# Driver.net
KiCad netlist of a schematic drawn in Altium Designer
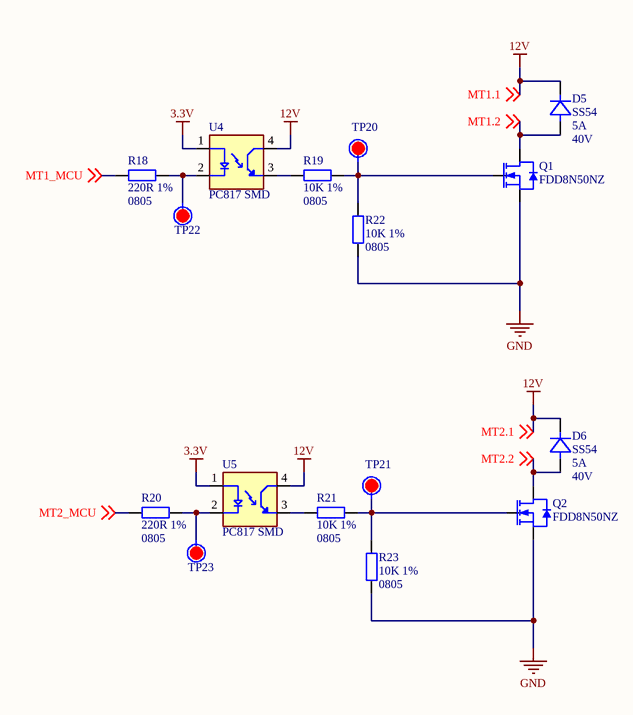
[diagram p0: Driver.SchDoc]

(export (version "E")
  (design (tool "Eeschema 10.0.6"))
  (components
    (comp (ref "D5")
      (value "SS54")
      (footprint "SMA")
      (description "DIODE SCHOTTKY 40V 5A SMA")
      (fields
        (field (name "MANUFACTURER") "EVVO")
        (field (name "CURRENT") "5A")
        (field (name "DC VOLTAGE") "40V")
      )
      (libsource (lib "Diode") (part "SS54"))
    )
    (comp (ref "D6")
      (value "SS54")
      (footprint "SMA")
      (description "DIODE SCHOTTKY 40V 5A SMA")
      (fields
        (field (name "MANUFACTURER") "EVVO")
        (field (name "CURRENT") "5A")
        (field (name "DC VOLTAGE") "40V")
      )
      (libsource (lib "Diode") (part "SS54"))
    )
    (comp (ref "Q1")
      (value "FDD8N50NZ")
      (footprint "TO252-2")
      (description "650V 7A 1 N-Channel TO-252 MOSFETs ROHS")
      (fields
        (field (name "MANUFACTURER") "VBsemi Elec")
        (field (name "MANUFACTURE PART NUMBER") "FDD8N50NZTM-VB")
      )
      (libsource (lib "Trans_Fets") (part "FDD8N50NZ"))
    )
    (comp (ref "Q2")
      (value "FDD8N50NZ")
      (footprint "TO252-2")
      (description "650V 7A 1 N-Channel TO-252 MOSFETs ROHS")
      (fields
        (field (name "MANUFACTURER") "VBsemi Elec")
        (field (name "MANUFACTURE PART NUMBER") "FDD8N50NZTM-VB")
      )
      (libsource (lib "Trans_Fets") (part "FDD8N50NZ"))
    )
    (comp (ref "R18")
      (value "220R 1%")
      (footprint "RES_SMD_0805")
      (fields
        (field (name "MANUFACTURER") "TE Connectivity Passive Product")
        (field (name "MANUFACTURE PART NUMBER") "CRGCQ0805F220R")
        (field (name "SIZE") "0805")
      )
      (libsource (lib "Resistors") (part "R0805_220R"))
    )
    (comp (ref "R19")
      (value "10K 1%")
      (footprint "RES_SMD_0805")
      (description "10 kOhms ±1% 0.125W, 1/8W Chip Resistor 0805 (2012 Metric) Moisture Resistant Thick Film")
      (fields
        (field (name "MANUFACTURER") "YAGEO")
        (field (name "MANUFACTURE PART NUMBER") "RC0805FR-0710KL")
        (field (name "SIZE") "0805")
      )
      (libsource (lib "Resistors") (part "R0805_10K"))
    )
    (comp (ref "R20")
      (value "220R 1%")
      (footprint "RES_SMD_0805")
      (fields
        (field (name "MANUFACTURER") "TE Connectivity Passive Product")
        (field (name "MANUFACTURE PART NUMBER") "CRGCQ0805F220R")
        (field (name "SIZE") "0805")
      )
      (libsource (lib "Resistors") (part "R0805_220R"))
    )
    (comp (ref "R21")
      (value "10K 1%")
      (footprint "RES_SMD_0805")
      (description "10 kOhms ±1% 0.125W, 1/8W Chip Resistor 0805 (2012 Metric) Moisture Resistant Thick Film")
      (fields
        (field (name "MANUFACTURER") "YAGEO")
        (field (name "MANUFACTURE PART NUMBER") "RC0805FR-0710KL")
        (field (name "SIZE") "0805")
      )
      (libsource (lib "Resistors") (part "R0805_10K"))
    )
    (comp (ref "R22")
      (value "10K 1%")
      (footprint "RES_SMD_0805")
      (description "10 kOhms ±1% 0.125W, 1/8W Chip Resistor 0805 (2012 Metric) Moisture Resistant Thick Film")
      (fields
        (field (name "MANUFACTURER") "YAGEO")
        (field (name "MANUFACTURE PART NUMBER") "RC0805FR-0710KL")
        (field (name "SIZE") "0805")
      )
      (libsource (lib "Resistors") (part "R0805_10K"))
    )
    (comp (ref "R23")
      (value "10K 1%")
      (footprint "RES_SMD_0805")
      (description "10 kOhms ±1% 0.125W, 1/8W Chip Resistor 0805 (2012 Metric) Moisture Resistant Thick Film")
      (fields
        (field (name "MANUFACTURER") "YAGEO")
        (field (name "MANUFACTURE PART NUMBER") "RC0805FR-0710KL")
        (field (name "SIZE") "0805")
      )
      (libsource (lib "Resistors") (part "R0805_10K"))
    )
    (comp (ref "TP20")
      (value "Test Point")
      (footprint "TEST_POINT")
      (libsource (lib "Connectors") (part "TEST_POINT"))
    )
    (comp (ref "TP21")
      (value "Test Point")
      (footprint "TEST_POINT")
      (libsource (lib "Connectors") (part "TEST_POINT"))
    )
    (comp (ref "TP22")
      (value "Test Point")
      (footprint "TEST_POINT")
      (libsource (lib "Connectors") (part "TEST_POINT"))
    )
    (comp (ref "TP23")
      (value "Test Point")
      (footprint "TEST_POINT")
      (libsource (lib "Connectors") (part "TEST_POINT"))
    )
    (comp (ref "U4")
      (value "PC817 SMD")
      (footprint "PC817XL_SMD")
      (description "Optoisolator Transistor Output 5000Vrms 1 Channel 4-SMD")
      (fields
        (field (name "MANUFACTURER") "American Bright Optoelectronics Corporation")
        (field (name "MANUFACTURE PART NUMBER") "APC-817C1-SL")
      )
      (libsource (lib "ICs") (part "PC817_SMD"))
    )
    (comp (ref "U5")
      (value "PC817 SMD")
      (footprint "PC817XL_SMD")
      (description "Optoisolator Transistor Output 5000Vrms 1 Channel 4-SMD")
      (fields
        (field (name "MANUFACTURER") "American Bright Optoelectronics Corporation")
        (field (name "MANUFACTURE PART NUMBER") "APC-817C1-SL")
      )
      (libsource (lib "ICs") (part "PC817_SMD"))
    )
  )
  (nets
    (net (code "1") (name "3.3V") (class "Default")
      (node (ref "U4") (pin "1") (pinfunction "A_1") (pintype "passive"))
      (node (ref "U5") (pin "1") (pinfunction "A_1") (pintype "passive"))
    )
    (net (code "2") (name "12V") (class "Default")
      (node (ref "D5") (pin "C") (pinfunction "C_C") (pintype "passive"))
      (node (ref "D6") (pin "C") (pinfunction "C_C") (pintype "passive"))
      (node (ref "U4") (pin "4") (pinfunction "CT_4") (pintype "passive"))
      (node (ref "U5") (pin "4") (pinfunction "CT_4") (pintype "passive"))
    )
    (net (code "3") (name "GND") (class "Default")
      (node (ref "Q1") (pin "3") (pinfunction "S_3") (pintype "passive"))
      (node (ref "Q2") (pin "3") (pinfunction "S_3") (pintype "passive"))
      (node (ref "R22") (pin "1") (pinfunction "1_1") (pintype "passive"))
      (node (ref "R23") (pin "1") (pinfunction "1_1") (pintype "passive"))
    )
    (net (code "4") (name "MT1.2") (class "Default")
      (node (ref "D5") (pin "A") (pinfunction "A_A") (pintype "passive"))
      (node (ref "Q1") (pin "2") (pinfunction "D_2") (pintype "passive"))
    )
    (net (code "5") (name "MT1_MCU") (class "Default")
      (node (ref "R18") (pin "2") (pinfunction "2_2") (pintype "passive"))
    )
    (net (code "6") (name "MT2.2") (class "Default")
      (node (ref "D6") (pin "A") (pinfunction "A_A") (pintype "passive"))
      (node (ref "Q2") (pin "2") (pinfunction "D_2") (pintype "passive"))
    )
    (net (code "7") (name "MT2_MCU") (class "Default")
      (node (ref "R20") (pin "2") (pinfunction "2_2") (pintype "passive"))
    )
    (net (code "8") (name "Net-(Q1-G)") (class "Default")
      (node (ref "Q1") (pin "1") (pinfunction "G_1") (pintype "passive"))
      (node (ref "R19") (pin "2") (pinfunction "2_2") (pintype "passive"))
      (node (ref "R22") (pin "2") (pinfunction "2_2") (pintype "passive"))
      (node (ref "TP20") (pin "1") (pinfunction "1_1") (pintype "passive"))
    )
    (net (code "9") (name "Net-(Q2-G)") (class "Default")
      (node (ref "Q2") (pin "1") (pinfunction "G_1") (pintype "passive"))
      (node (ref "R21") (pin "2") (pinfunction "2_2") (pintype "passive"))
      (node (ref "R23") (pin "2") (pinfunction "2_2") (pintype "passive"))
      (node (ref "TP21") (pin "1") (pinfunction "1_1") (pintype "passive"))
    )
    (net (code "10") (name "Net-(U4-C)") (class "Default")
      (node (ref "R18") (pin "1") (pinfunction "1_1") (pintype "passive"))
      (node (ref "TP22") (pin "1") (pinfunction "1_1") (pintype "passive"))
      (node (ref "U4") (pin "2") (pinfunction "C_2") (pintype "passive"))
    )
    (net (code "11") (name "Net-(U4-ET)") (class "Default")
      (node (ref "R19") (pin "1") (pinfunction "1_1") (pintype "passive"))
      (node (ref "U4") (pin "3") (pinfunction "ET_3") (pintype "passive"))
    )
    (net (code "12") (name "Net-(U5-C)") (class "Default")
      (node (ref "R20") (pin "1") (pinfunction "1_1") (pintype "passive"))
      (node (ref "TP23") (pin "1") (pinfunction "1_1") (pintype "passive"))
      (node (ref "U5") (pin "2") (pinfunction "C_2") (pintype "passive"))
    )
    (net (code "13") (name "Net-(U5-ET)") (class "Default")
      (node (ref "R21") (pin "1") (pinfunction "1_1") (pintype "passive"))
      (node (ref "U5") (pin "3") (pinfunction "ET_3") (pintype "passive"))
    )
  )
)
